# untitled.net
KiCad netlist of a schematic drawn in EAGLE
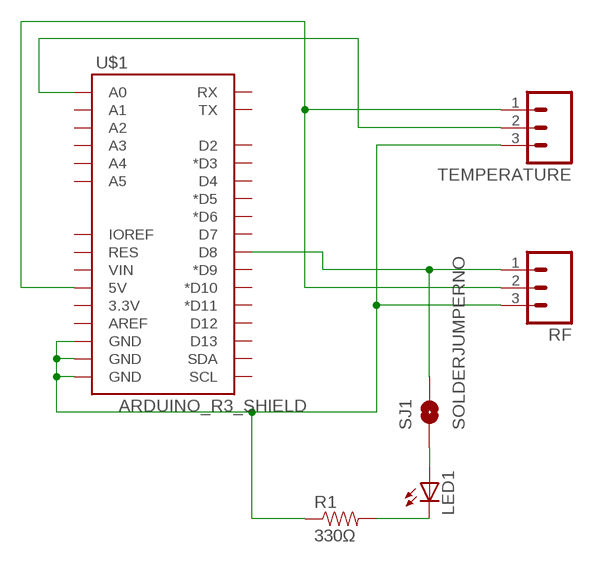
[diagram p0: schematic, sheet 1]

(export (version "E")
  (design (tool "Eeschema 10.0.6"))
  (components
    (comp (ref "LED1")
      (value "LED5MM")
      (footprint "eagle-import:LED5MM")
      (libsource (lib "eagle-import") (part "LED5MM"))
    )
    (comp (ref "R1")
      (value "330Ω")
      (footprint "eagle-import:AXIAL-0.3")
      (libsource (lib "eagle-import") (part "10KOHM-1/4W-1%(PTH)HORIZ"))
    )
    (comp (ref "RF")
      (value "M03LONGPADS")
      (footprint "eagle-import:1X03_LONGPADS")
      (libsource (lib "eagle-import") (part "M03LONGPADS"))
    )
    (comp (ref "SJ1")
      (value "SOLDERJUMPERNO")
      (footprint "eagle-import:SJ_2S-NO")
      (libsource (lib "eagle-import") (part "SOLDERJUMPERNO"))
    )
    (comp (ref "TEMPERATURE")
      (value "M03LONGPADS")
      (footprint "eagle-import:1X03_LONGPADS")
      (libsource (lib "eagle-import") (part "M03LONGPADS"))
    )
    (comp (ref "U$1")
      (value "ARDUINO_R3_SHIELD")
      (footprint "eagle-import:UNO_R3_SHIELD")
      (libsource (lib "eagle-import") (part "ARDUINO_R3_SHIELD"))
    )
  )
  (nets
    (net (code "1") (name "Net-(LED1-C)") (class "Default")
      (node (ref "LED1") (pin "K") (pinfunction "C_K") (pintype "passive"))
      (node (ref "R1") (pin "P$2") (pinfunction "2_P$2") (pintype "passive"))
    )
    (net (code "2") (name "Net-(LED1-PadA)") (class "Default")
      (node (ref "LED1") (pin "A") (pinfunction "A_A") (pintype "passive"))
      (node (ref "SJ1") (pin "1") (pinfunction "1_1") (pintype "passive"))
    )
    (net (code "3") (name "Net-(R1-1)") (class "Default")
      (node (ref "R1") (pin "P$1") (pinfunction "1_P$1") (pintype "passive"))
      (node (ref "RF") (pin "3") (pinfunction "3_3") (pintype "passive"))
      (node (ref "TEMPERATURE") (pin "3") (pinfunction "3_3") (pintype "passive"))
      (node (ref "U$1") (pin "GND@0") (pinfunction "GND_GND@0") (pintype "bidirectional"))
      (node (ref "U$1") (pin "GND@1") (pinfunction "GND_GND@1") (pintype "bidirectional"))
      (node (ref "U$1") (pin "GND@2") (pinfunction "GND_GND@2") (pintype "bidirectional"))
    )
    (net (code "4") (name "Net-(RF-Pad1)") (class "Default")
      (node (ref "RF") (pin "1") (pinfunction "1_1") (pintype "passive"))
      (node (ref "SJ1") (pin "2") (pinfunction "2_2") (pintype "passive"))
      (node (ref "U$1") (pin "D8") (pinfunction "D8_D8") (pintype "bidirectional"))
    )
    (net (code "5") (name "Net-(RF-Pad2)") (class "Default")
      (node (ref "RF") (pin "2") (pinfunction "2_2") (pintype "passive"))
      (node (ref "TEMPERATURE") (pin "1") (pinfunction "1_1") (pintype "passive"))
      (node (ref "U$1") (pin "5V") (pinfunction "5V_5V") (pintype "bidirectional"))
    )
    (net (code "6") (name "Net-(TEMPERATURE-Pad2)") (class "Default")
      (node (ref "TEMPERATURE") (pin "2") (pinfunction "2_2") (pintype "passive"))
      (node (ref "U$1") (pin "A0") (pinfunction "A0_A0") (pintype "bidirectional"))
    )
    (net (code "7") (name "unconnected-(U$1-*D3-PadD3)") (class "Default")
      (node (ref "U$1") (pin "D3") (pinfunction "*D3_D3") (pintype "bidirectional"))
    )
    (net (code "8") (name "unconnected-(U$1-*D5-PadD5)") (class "Default")
      (node (ref "U$1") (pin "D5") (pinfunction "*D5_D5") (pintype "bidirectional"))
    )
    (net (code "9") (name "unconnected-(U$1-*D6-PadD6)") (class "Default")
      (node (ref "U$1") (pin "D6") (pinfunction "*D6_D6") (pintype "bidirectional"))
    )
    (net (code "10") (name "unconnected-(U$1-*D9-PadD9)") (class "Default")
      (node (ref "U$1") (pin "D9") (pinfunction "*D9_D9") (pintype "bidirectional"))
    )
    (net (code "11") (name "unconnected-(U$1-*D10-PadD10)") (class "Default")
      (node (ref "U$1") (pin "D10") (pinfunction "*D10_D10") (pintype "bidirectional"))
    )
    (net (code "12") (name "unconnected-(U$1-*D11-PadD11)") (class "Default")
      (node (ref "U$1") (pin "D11") (pinfunction "*D11_D11") (pintype "bidirectional"))
    )
    (net (code "13") (name "unconnected-(U$1-Pad3.3V)") (class "Default")
      (node (ref "U$1") (pin "3.3V") (pinfunction "3.3V_3.3V") (pintype "bidirectional"))
    )
    (net (code "14") (name "unconnected-(U$1-PadA1)") (class "Default")
      (node (ref "U$1") (pin "A1") (pinfunction "A1_A1") (pintype "bidirectional"))
    )
    (net (code "15") (name "unconnected-(U$1-PadA2)") (class "Default")
      (node (ref "U$1") (pin "A2") (pinfunction "A2_A2") (pintype "bidirectional"))
    )
    (net (code "16") (name "unconnected-(U$1-PadA3)") (class "Default")
      (node (ref "U$1") (pin "A3") (pinfunction "A3_A3") (pintype "bidirectional"))
    )
    (net (code "17") (name "unconnected-(U$1-PadA4)") (class "Default")
      (node (ref "U$1") (pin "A4") (pinfunction "A4_A4") (pintype "bidirectional"))
    )
    (net (code "18") (name "unconnected-(U$1-PadA5)") (class "Default")
      (node (ref "U$1") (pin "A5") (pinfunction "A5_A5") (pintype "bidirectional"))
    )
    (net (code "19") (name "unconnected-(U$1-PadAREF)") (class "Default")
      (node (ref "U$1") (pin "AREF") (pinfunction "AREF_AREF") (pintype "bidirectional"))
    )
    (net (code "20") (name "unconnected-(U$1-PadD2)") (class "Default")
      (node (ref "U$1") (pin "D2") (pinfunction "D2_D2") (pintype "bidirectional"))
    )
    (net (code "21") (name "unconnected-(U$1-PadD4)") (class "Default")
      (node (ref "U$1") (pin "D4") (pinfunction "D4_D4") (pintype "bidirectional"))
    )
    (net (code "22") (name "unconnected-(U$1-PadD7)") (class "Default")
      (node (ref "U$1") (pin "D7") (pinfunction "D7_D7") (pintype "bidirectional"))
    )
    (net (code "23") (name "unconnected-(U$1-PadD12)") (class "Default")
      (node (ref "U$1") (pin "D12") (pinfunction "D12_D12") (pintype "bidirectional"))
    )
    (net (code "24") (name "unconnected-(U$1-PadD13)") (class "Default")
      (node (ref "U$1") (pin "D13") (pinfunction "D13_D13") (pintype "bidirectional"))
    )
    (net (code "25") (name "unconnected-(U$1-PadIOREF)") (class "Default")
      (node (ref "U$1") (pin "IOREF") (pinfunction "IOREF_IOREF") (pintype "bidirectional"))
    )
    (net (code "26") (name "unconnected-(U$1-PadRES)") (class "Default")
      (node (ref "U$1") (pin "RES") (pinfunction "RES_RES") (pintype "bidirectional"))
    )
    (net (code "27") (name "unconnected-(U$1-PadRX)") (class "Default")
      (node (ref "U$1") (pin "RX") (pinfunction "RX_RX") (pintype "bidirectional"))
    )
    (net (code "28") (name "unconnected-(U$1-PadSCL)") (class "Default")
      (node (ref "U$1") (pin "SCL") (pinfunction "SCL_SCL") (pintype "bidirectional"))
    )
    (net (code "29") (name "unconnected-(U$1-PadSDA)") (class "Default")
      (node (ref "U$1") (pin "SDA") (pinfunction "SDA_SDA") (pintype "bidirectional"))
    )
    (net (code "30") (name "unconnected-(U$1-PadTX)") (class "Default")
      (node (ref "U$1") (pin "TX") (pinfunction "TX_TX") (pintype "bidirectional"))
    )
    (net (code "31") (name "unconnected-(U$1-PadVIN)") (class "Default")
      (node (ref "U$1") (pin "VIN") (pinfunction "VIN_VIN") (pintype "bidirectional"))
    )
  )
)
